# interconnect_RA_V1_2.net
KiCad netlist of a schematic drawn in EAGLE
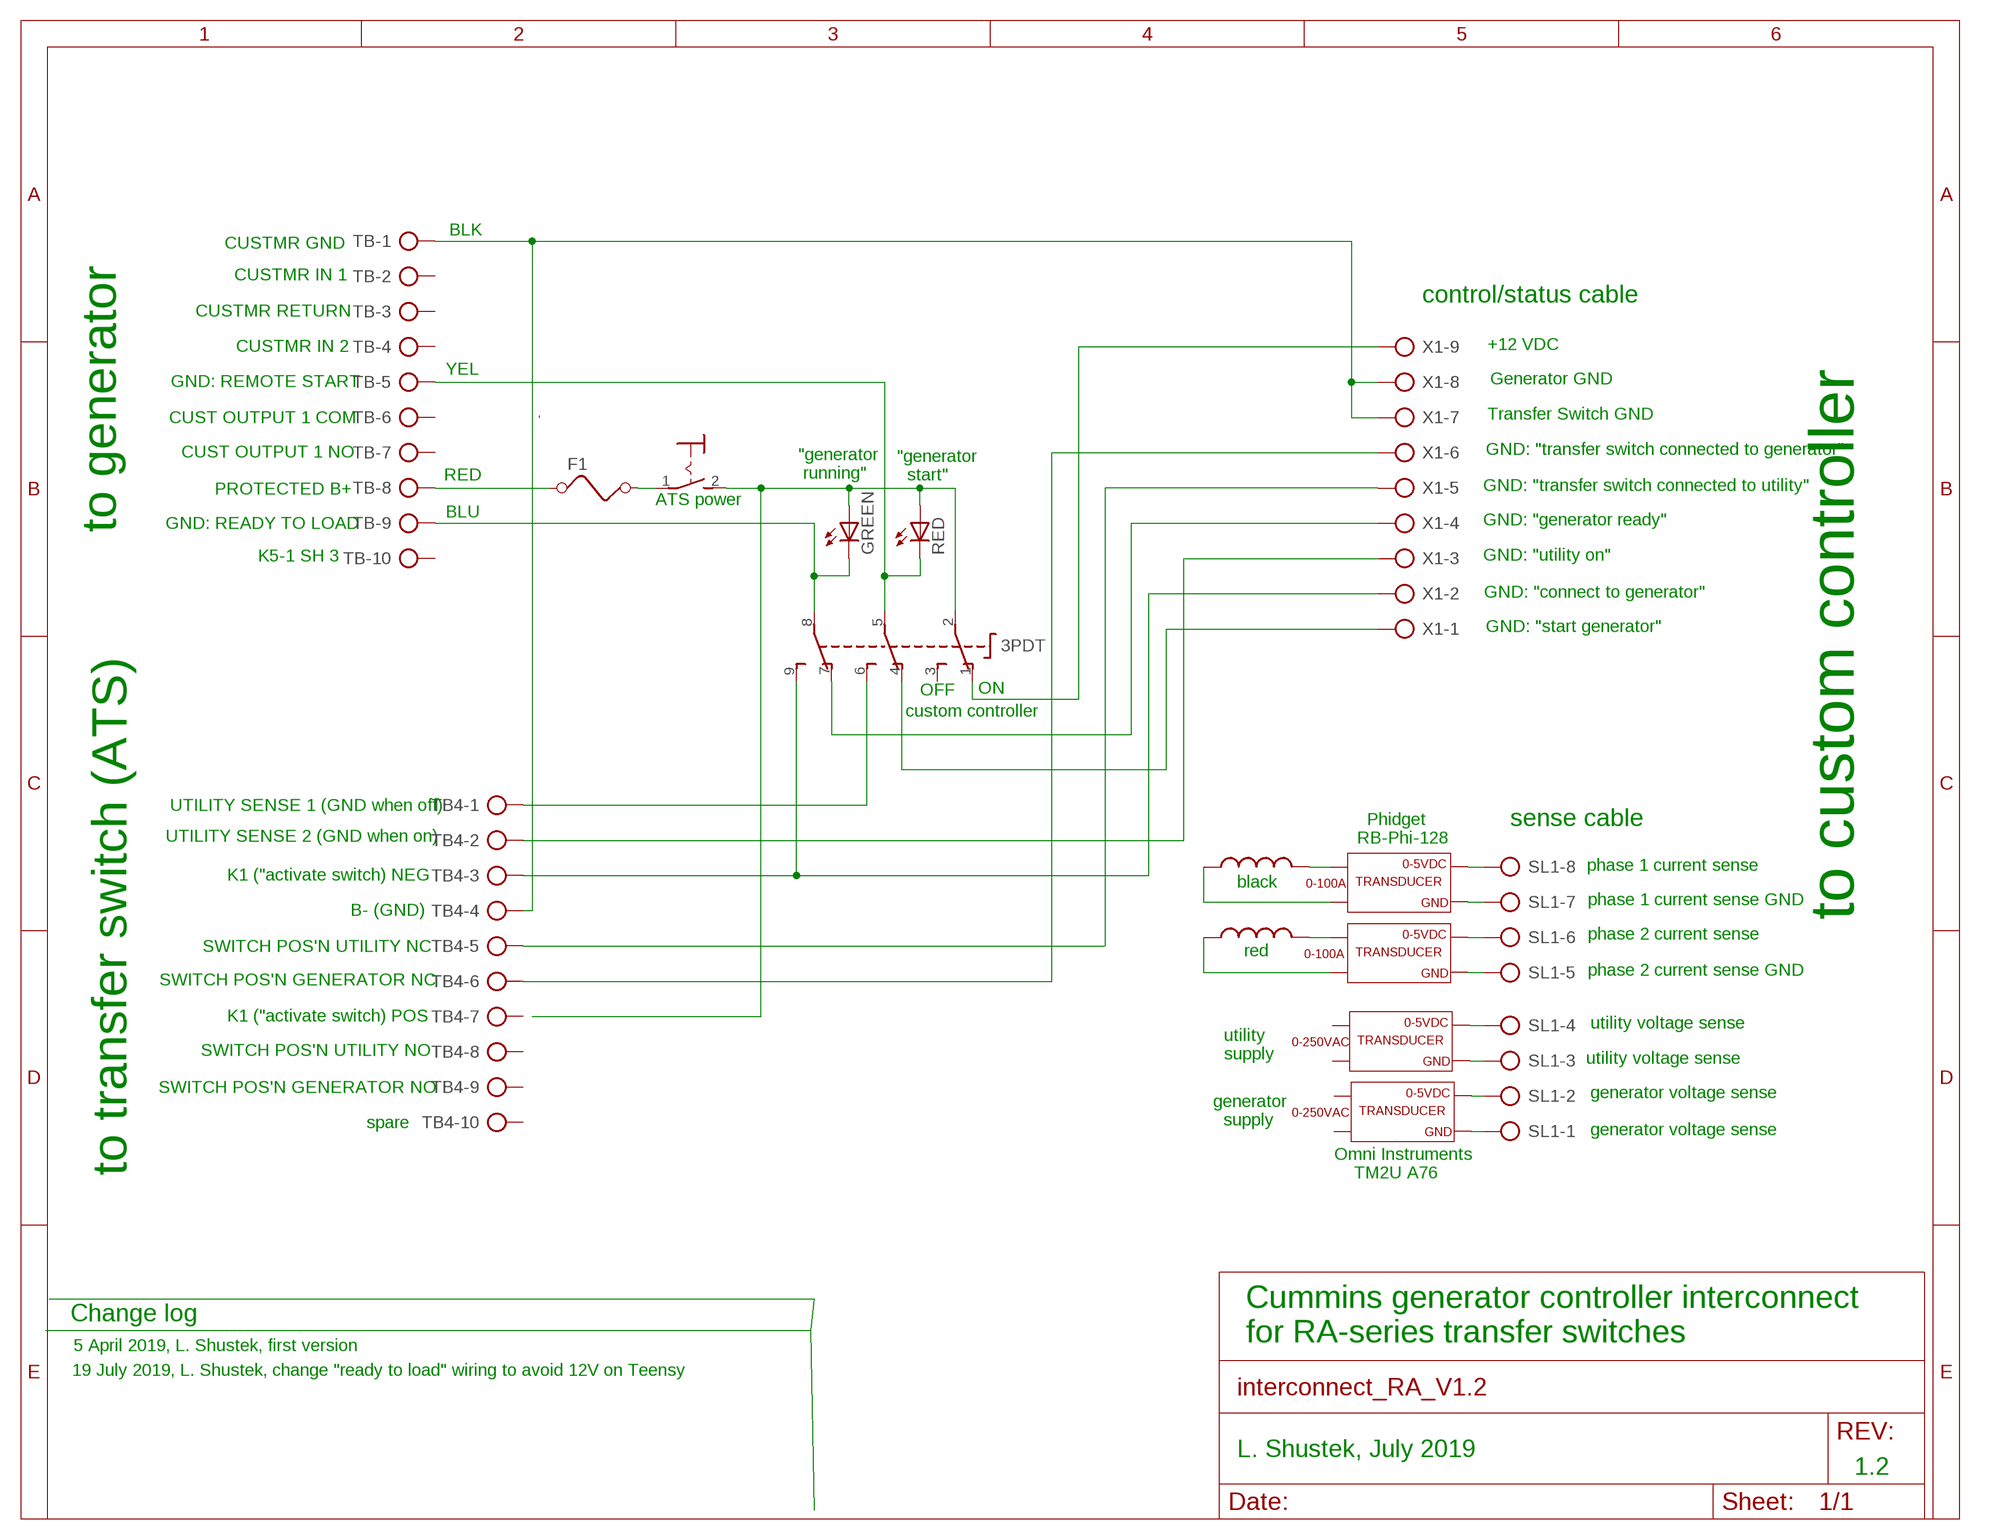
[diagram p0: schematic, sheet 1]

(export (version "E")
  (design (tool "Eeschema 10.0.6"))
  (components
    (comp (ref "F1")
      (value "FUSE")
      (footprint "eagle-import:FUSE")
      (libsource (lib "eagle-import") (part "FUSE"))
    )
    (comp (ref "GREEN")
      (value "LED")
      (footprint "eagle-import:SMARTLED-TTW")
      (libsource (lib "eagle-import") (part "LED"))
    )
    (comp (ref "L1")
      (value "L-US0204/5")
      (footprint "eagle-import:0204_5")
      (libsource (lib "eagle-import") (part "L-US0204/5"))
    )
    (comp (ref "L2")
      (value "L-US0204/5")
      (footprint "eagle-import:0204_5")
      (libsource (lib "eagle-import") (part "L-US0204/5"))
    )
    (comp (ref "RED")
      (value "LED")
      (footprint "eagle-import:SMARTLED-TTW")
      (libsource (lib "eagle-import") (part "LED"))
    )
    (comp (ref "S1")
      (value "MS243")
      (footprint "eagle-import:MS243")
      (libsource (lib "eagle-import") (part "MS243"))
    )
    (comp (ref "S2")
      (value "3PDT")
      (footprint "eagle-import:3PDT")
      (libsource (lib "eagle-import") (part "3PDT"))
    )
    (comp (ref "SL1")
      (value "AK500/8")
      (footprint "eagle-import:AK500_8")
      (libsource (lib "eagle-import") (part "AK500/8"))
    )
    (comp (ref "TB")
      (value "AK500/10")
      (footprint "eagle-import:AK500_10")
      (libsource (lib "eagle-import") (part "AK500/10"))
    )
    (comp (ref "TB4")
      (value "AK500/10")
      (footprint "eagle-import:AK500_10")
      (libsource (lib "eagle-import") (part "AK500/10"))
    )
    (comp (ref "U$1")
      (value "0-100A")
      (footprint "eagle-import:TRANSDUCER")
      (libsource (lib "eagle-import") (part "TRANSDUCER"))
    )
    (comp (ref "U$2")
      (value "0-100A")
      (footprint "eagle-import:TRANSDUCER")
      (libsource (lib "eagle-import") (part "TRANSDUCER"))
    )
    (comp (ref "U$3")
      (value "0-250VAC")
      (footprint "eagle-import:TRANSDUCER")
      (libsource (lib "eagle-import") (part "TRANSDUCER"))
    )
    (comp (ref "U$4")
      (value "0-250VAC")
      (footprint "eagle-import:TRANSDUCER")
      (libsource (lib "eagle-import") (part "TRANSDUCER"))
    )
    (comp (ref "X1")
      (value "AK500/9")
      (footprint "eagle-import:AK500_9")
      (libsource (lib "eagle-import") (part "AK500/9"))
    )
  )
  (nets
    (net (code "1") (name "Net-(GREEN-A)") (class "Default")
      (node (ref "GREEN") (pin "A@1") (pinfunction "A_A@1") (pintype "passive"))
      (node (ref "RED") (pin "A@1") (pinfunction "A_A@1") (pintype "passive"))
      (node (ref "S1") (pin "2") (pinfunction "S_2") (pintype "passive"))
      (node (ref "S2") (pin "2") (pinfunction "P1_2") (pintype "passive"))
    )
    (net (code "2") (name "Net-(GREEN-C)") (class "Default")
      (node (ref "GREEN") (pin "C@1") (pinfunction "C_C@1") (pintype "passive"))
      (node (ref "S2") (pin "8") (pinfunction "P3_8") (pintype "passive"))
      (node (ref "TB") (pin "9") (pinfunction "KL_9") (pintype "passive"))
    )
    (net (code "3") (name "Net-(L1-Pad1)") (class "Default")
      (node (ref "L1") (pin "1") (pinfunction "1_1") (pintype "passive"))
      (node (ref "U$1") (pin "P$2") (pinfunction "P$2_P$2") (pintype "bidirectional"))
    )
    (net (code "4") (name "Net-(L1-Pad2)") (class "Default")
      (node (ref "L1") (pin "2") (pinfunction "2_2") (pintype "passive"))
      (node (ref "U$1") (pin "P$1") (pinfunction "P$1_P$1") (pintype "bidirectional"))
    )
    (net (code "5") (name "Net-(L2-Pad1)") (class "Default")
      (node (ref "L2") (pin "1") (pinfunction "1_1") (pintype "passive"))
      (node (ref "U$2") (pin "P$2") (pinfunction "P$2_P$2") (pintype "bidirectional"))
    )
    (net (code "6") (name "Net-(L2-Pad2)") (class "Default")
      (node (ref "L2") (pin "2") (pinfunction "2_2") (pintype "passive"))
      (node (ref "U$2") (pin "P$1") (pinfunction "P$1_P$1") (pintype "bidirectional"))
    )
    (net (code "7") (name "Net-(RED-C)") (class "Default")
      (node (ref "RED") (pin "C@1") (pinfunction "C_C@1") (pintype "passive"))
      (node (ref "S2") (pin "5") (pinfunction "P2_5") (pintype "passive"))
      (node (ref "TB") (pin "5") (pinfunction "KL_5") (pintype "passive"))
    )
    (net (code "8") (name "Net-(S1-P)") (class "Default")
      (node (ref "F1") (pin "2") (pinfunction "2_2") (pintype "passive"))
      (node (ref "S1") (pin "1") (pinfunction "P_1") (pintype "passive"))
    )
    (net (code "9") (name "Net-(S2-O1)") (class "Default")
      (node (ref "S2") (pin "1") (pinfunction "O1_1") (pintype "passive"))
      (node (ref "X1") (pin "9") (pinfunction "KL_9") (pintype "passive"))
    )
    (net (code "10") (name "Net-(S2-O2)") (class "Default")
      (node (ref "S2") (pin "4") (pinfunction "O2_4") (pintype "passive"))
      (node (ref "X1") (pin "1") (pinfunction "KL_1") (pintype "passive"))
    )
    (net (code "11") (name "Net-(S2-O3)") (class "Default")
      (node (ref "S2") (pin "7") (pinfunction "O3_7") (pintype "passive"))
      (node (ref "X1") (pin "4") (pinfunction "KL_4") (pintype "passive"))
    )
    (net (code "12") (name "Net-(S2-S2)") (class "Default")
      (node (ref "S2") (pin "6") (pinfunction "S2_6") (pintype "passive"))
      (node (ref "TB4") (pin "1") (pinfunction "KL_1") (pintype "passive"))
    )
    (net (code "13") (name "Net-(S2-S3)") (class "Default")
      (node (ref "S2") (pin "9") (pinfunction "S3_9") (pintype "passive"))
      (node (ref "TB4") (pin "3") (pinfunction "KL_3") (pintype "passive"))
      (node (ref "X1") (pin "2") (pinfunction "KL_2") (pintype "passive"))
    )
    (net (code "14") (name "Net-(SL1A-KL)") (class "Default")
      (node (ref "SL1") (pin "1") (pinfunction "KL_1") (pintype "passive"))
      (node (ref "U$4") (pin "P$4") (pinfunction "P$4_P$4") (pintype "bidirectional"))
    )
    (net (code "15") (name "Net-(SL1B-KL)") (class "Default")
      (node (ref "SL1") (pin "2") (pinfunction "KL_2") (pintype "passive"))
      (node (ref "U$4") (pin "P$3") (pinfunction "P$3_P$3") (pintype "bidirectional"))
    )
    (net (code "16") (name "Net-(SL1C-KL)") (class "Default")
      (node (ref "SL1") (pin "3") (pinfunction "KL_3") (pintype "passive"))
      (node (ref "U$3") (pin "P$4") (pinfunction "P$4_P$4") (pintype "bidirectional"))
    )
    (net (code "17") (name "Net-(SL1D-KL)") (class "Default")
      (node (ref "SL1") (pin "4") (pinfunction "KL_4") (pintype "passive"))
      (node (ref "U$3") (pin "P$3") (pinfunction "P$3_P$3") (pintype "bidirectional"))
    )
    (net (code "18") (name "Net-(SL1E-KL)") (class "Default")
      (node (ref "SL1") (pin "5") (pinfunction "KL_5") (pintype "passive"))
      (node (ref "U$2") (pin "P$4") (pinfunction "P$4_P$4") (pintype "bidirectional"))
    )
    (net (code "19") (name "Net-(SL1F-KL)") (class "Default")
      (node (ref "SL1") (pin "6") (pinfunction "KL_6") (pintype "passive"))
      (node (ref "U$2") (pin "P$3") (pinfunction "P$3_P$3") (pintype "bidirectional"))
    )
    (net (code "20") (name "Net-(SL1G-KL)") (class "Default")
      (node (ref "SL1") (pin "7") (pinfunction "KL_7") (pintype "passive"))
      (node (ref "U$1") (pin "P$4") (pinfunction "P$4_P$4") (pintype "bidirectional"))
    )
    (net (code "21") (name "Net-(SL1H-KL)") (class "Default")
      (node (ref "SL1") (pin "8") (pinfunction "KL_8") (pintype "passive"))
      (node (ref "U$1") (pin "P$3") (pinfunction "P$3_P$3") (pintype "bidirectional"))
    )
    (net (code "22") (name "Net-(TB4C-KL)") (class "Default")
      (node (ref "TB4") (pin "2") (pinfunction "KL_2") (pintype "passive"))
      (node (ref "X1") (pin "3") (pinfunction "KL_3") (pintype "passive"))
    )
    (net (code "23") (name "Net-(TB4E-KL)") (class "Default")
      (node (ref "TB") (pin "1") (pinfunction "KL_1") (pintype "passive"))
      (node (ref "TB4") (pin "4") (pinfunction "KL_4") (pintype "passive"))
      (node (ref "X1") (pin "7") (pinfunction "KL_7") (pintype "passive"))
      (node (ref "X1") (pin "8") (pinfunction "KL_8") (pintype "passive"))
    )
    (net (code "24") (name "Net-(TB4F-KL)") (class "Default")
      (node (ref "TB4") (pin "5") (pinfunction "KL_5") (pintype "passive"))
      (node (ref "X1") (pin "5") (pinfunction "KL_5") (pintype "passive"))
    )
    (net (code "25") (name "Net-(TB4G-KL)") (class "Default")
      (node (ref "TB4") (pin "6") (pinfunction "KL_6") (pintype "passive"))
      (node (ref "X1") (pin "6") (pinfunction "KL_6") (pintype "passive"))
    )
    (net (code "26") (name "Net-(TBI-KL)") (class "Default")
      (node (ref "F1") (pin "1") (pinfunction "1_1") (pintype "passive"))
      (node (ref "TB") (pin "8") (pinfunction "KL_8") (pintype "passive"))
    )
    (net (code "27") (name "unconnected-(S2-S1-Pad3)") (class "Default")
      (node (ref "S2") (pin "3") (pinfunction "S1_3") (pintype "passive"))
    )
    (net (code "28") (name "unconnected-(TB4B-KL-Pad10)") (class "Default")
      (node (ref "TB4") (pin "10") (pinfunction "KL_10") (pintype "passive"))
    )
    (net (code "29") (name "unconnected-(TB4H-KL-Pad7)") (class "Default")
      (node (ref "TB4") (pin "7") (pinfunction "KL_7") (pintype "passive"))
    )
    (net (code "30") (name "unconnected-(TB4I-KL-Pad8)") (class "Default")
      (node (ref "TB4") (pin "8") (pinfunction "KL_8") (pintype "passive"))
    )
    (net (code "31") (name "unconnected-(TB4J-KL-Pad9)") (class "Default")
      (node (ref "TB4") (pin "9") (pinfunction "KL_9") (pintype "passive"))
    )
    (net (code "32") (name "unconnected-(TBB-KL-Pad10)") (class "Default")
      (node (ref "TB") (pin "10") (pinfunction "KL_10") (pintype "passive"))
    )
    (net (code "33") (name "unconnected-(TBC-KL-Pad2)") (class "Default")
      (node (ref "TB") (pin "2") (pinfunction "KL_2") (pintype "passive"))
    )
    (net (code "34") (name "unconnected-(TBD-KL-Pad3)") (class "Default")
      (node (ref "TB") (pin "3") (pinfunction "KL_3") (pintype "passive"))
    )
    (net (code "35") (name "unconnected-(TBE-KL-Pad4)") (class "Default")
      (node (ref "TB") (pin "4") (pinfunction "KL_4") (pintype "passive"))
    )
    (net (code "36") (name "unconnected-(TBG-KL-Pad6)") (class "Default")
      (node (ref "TB") (pin "6") (pinfunction "KL_6") (pintype "passive"))
    )
    (net (code "37") (name "unconnected-(TBH-KL-Pad7)") (class "Default")
      (node (ref "TB") (pin "7") (pinfunction "KL_7") (pintype "passive"))
    )
    (net (code "38") (name "unconnected-(U$3-PadP$1)") (class "Default")
      (node (ref "U$3") (pin "P$1") (pinfunction "P$1_P$1") (pintype "bidirectional"))
    )
    (net (code "39") (name "unconnected-(U$3-PadP$2)") (class "Default")
      (node (ref "U$3") (pin "P$2") (pinfunction "P$2_P$2") (pintype "bidirectional"))
    )
    (net (code "40") (name "unconnected-(U$4-PadP$1)") (class "Default")
      (node (ref "U$4") (pin "P$1") (pinfunction "P$1_P$1") (pintype "bidirectional"))
    )
    (net (code "41") (name "unconnected-(U$4-PadP$2)") (class "Default")
      (node (ref "U$4") (pin "P$2") (pinfunction "P$2_P$2") (pintype "bidirectional"))
    )
  )
)
